# Dual_4-1_Mux.net
KiCad netlist of a schematic drawn in EAGLE
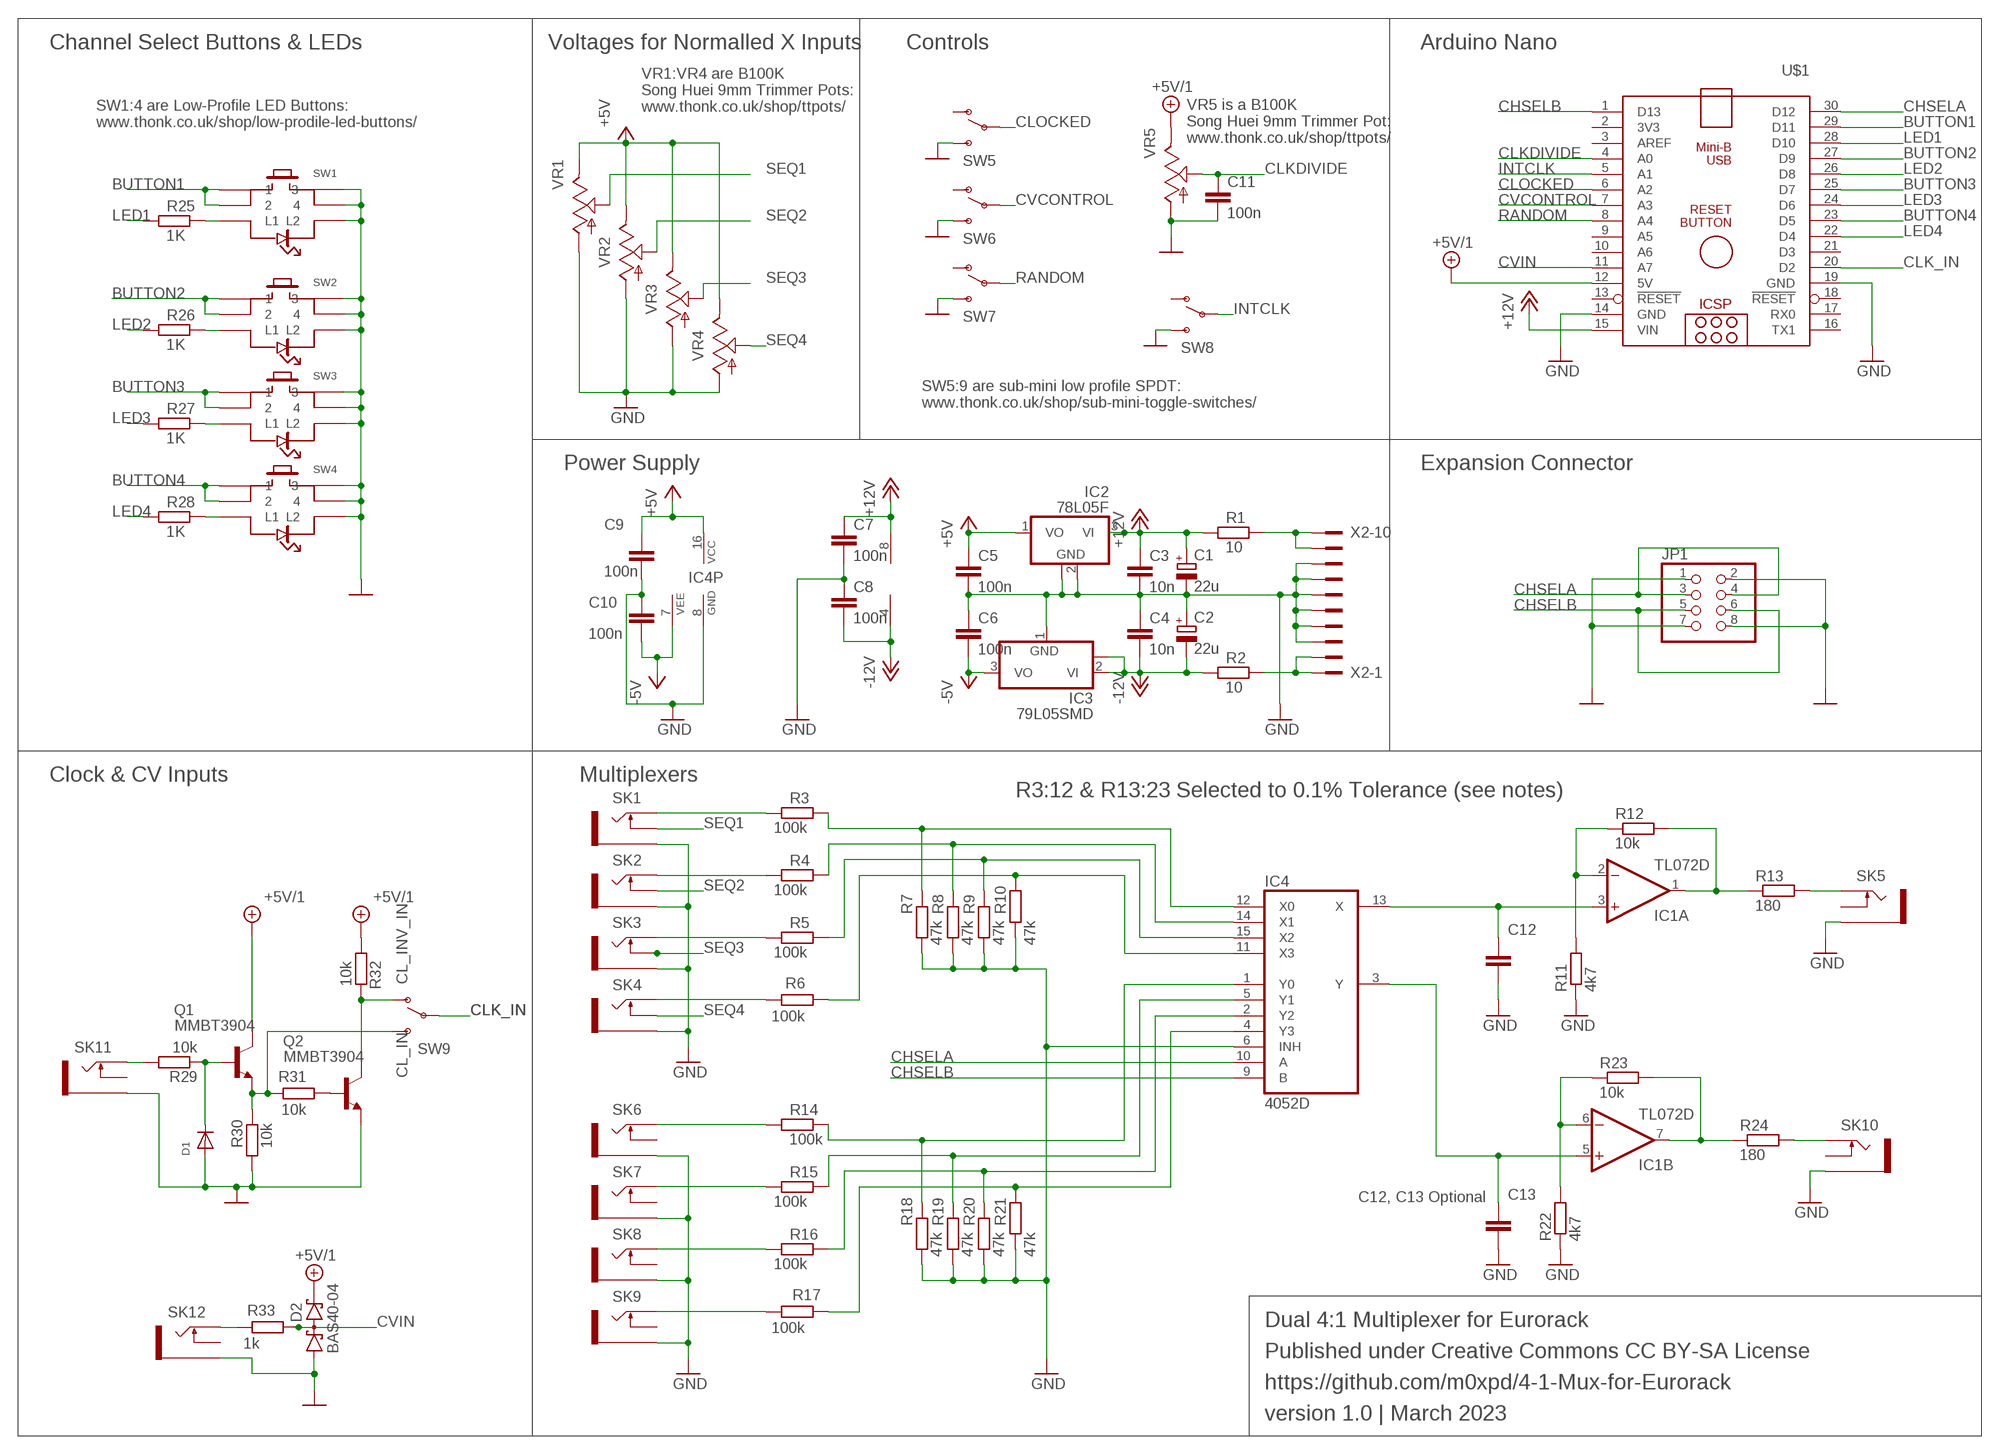
[diagram p0: schematic, sheet 1]

(export (version "E")
  (design (tool "Eeschema 10.0.6"))
  (components
    (comp (ref "C1")
      (value "22u")
      (footprint "eagle-import:153CLV-0505")
      (libsource (lib "eagle-import") (part "CPOL-EU153CLV-0505"))
    )
    (comp (ref "C2")
      (value "22u")
      (footprint "eagle-import:153CLV-0505")
      (libsource (lib "eagle-import") (part "CPOL-EU153CLV-0505"))
    )
    (comp (ref "C3")
      (value "10n")
      (footprint "eagle-import:C1206")
      (libsource (lib "eagle-import") (part "C-EUC1206"))
    )
    (comp (ref "C4")
      (value "10n")
      (footprint "eagle-import:C1206")
      (libsource (lib "eagle-import") (part "C-EUC1206"))
    )
    (comp (ref "C5")
      (value "100n")
      (footprint "eagle-import:C1206")
      (libsource (lib "eagle-import") (part "C-EUC1206"))
    )
    (comp (ref "C6")
      (value "100n")
      (footprint "eagle-import:C1206")
      (libsource (lib "eagle-import") (part "C-EUC1206"))
    )
    (comp (ref "C7")
      (value "100n")
      (footprint "eagle-import:C1206")
      (libsource (lib "eagle-import") (part "C-EUC1206"))
    )
    (comp (ref "C8")
      (value "100n")
      (footprint "eagle-import:C1206")
      (libsource (lib "eagle-import") (part "C-EUC1206"))
    )
    (comp (ref "C9")
      (value "100n")
      (footprint "eagle-import:C1206")
      (libsource (lib "eagle-import") (part "C-EUC1206"))
    )
    (comp (ref "C10")
      (value "100n")
      (footprint "eagle-import:C1206")
      (libsource (lib "eagle-import") (part "C-EUC1206"))
    )
    (comp (ref "C11")
      (value "100n")
      (footprint "eagle-import:C1206")
      (libsource (lib "eagle-import") (part "C-EUC1206"))
    )
    (comp (ref "C12")
      (value "C-EUC1206")
      (footprint "eagle-import:C1206")
      (libsource (lib "eagle-import") (part "C-EUC1206"))
    )
    (comp (ref "C13")
      (value "C-EUC1206")
      (footprint "eagle-import:C1206")
      (libsource (lib "eagle-import") (part "C-EUC1206"))
    )
    (comp (ref "D1")
      (value "DIODESOD-323F")
      (footprint "eagle-import:SOD-323F")
      (libsource (lib "eagle-import") (part "DIODESOD-323F"))
    )
    (comp (ref "D2")
      (value "BAS40-04")
      (footprint "eagle-import:SOT23")
      (libsource (lib "eagle-import") (part "BAS40-04"))
    )
    (comp (ref "IC1")
      (value "TL072D")
      (footprint "eagle-import:SO08")
      (libsource (lib "eagle-import") (part "TL072D"))
    )
    (comp (ref "IC2")
      (value "78L05F")
      (footprint "eagle-import:SOT89")
      (libsource (lib "eagle-import") (part "78LF05"))
    )
    (comp (ref "IC3")
      (value "79L05SMD")
      (footprint "eagle-import:SOT89")
      (libsource (lib "eagle-import") (part "79L05SMD"))
    )
    (comp (ref "IC4")
      (value "4052D")
      (footprint "eagle-import:SO16")
      (libsource (lib "eagle-import") (part "4052D"))
    )
    (comp (ref "JP1")
      (value "PINHD-2X4")
      (footprint "eagle-import:2X04")
      (libsource (lib "eagle-import") (part "PINHD-2X4"))
    )
    (comp (ref "Q1")
      (value "MMBT3904")
      (footprint "eagle-import:SOT23")
      (libsource (lib "eagle-import") (part "MMBT3904"))
    )
    (comp (ref "Q2")
      (value "MMBT3904")
      (footprint "eagle-import:SOT23")
      (libsource (lib "eagle-import") (part "MMBT3904"))
    )
    (comp (ref "R1")
      (value "10")
      (footprint "eagle-import:M1206")
      (libsource (lib "eagle-import") (part "R-EU_M1206"))
    )
    (comp (ref "R2")
      (value "10")
      (footprint "eagle-import:M1206")
      (libsource (lib "eagle-import") (part "R-EU_M1206"))
    )
    (comp (ref "R3")
      (value "100k")
      (footprint "eagle-import:M1206")
      (libsource (lib "eagle-import") (part "R-EU_M1206"))
    )
    (comp (ref "R4")
      (value "100k")
      (footprint "eagle-import:M1206")
      (libsource (lib "eagle-import") (part "R-EU_M1206"))
    )
    (comp (ref "R5")
      (value "100k")
      (footprint "eagle-import:M1206")
      (libsource (lib "eagle-import") (part "R-EU_M1206"))
    )
    (comp (ref "R6")
      (value "100k")
      (footprint "eagle-import:M1206")
      (libsource (lib "eagle-import") (part "R-EU_M1206"))
    )
    (comp (ref "R7")
      (value "47k")
      (footprint "eagle-import:M1206")
      (libsource (lib "eagle-import") (part "R-EU_M1206"))
    )
    (comp (ref "R8")
      (value "47k")
      (footprint "eagle-import:M1206")
      (libsource (lib "eagle-import") (part "R-EU_M1206"))
    )
    (comp (ref "R9")
      (value "47k")
      (footprint "eagle-import:M1206")
      (libsource (lib "eagle-import") (part "R-EU_M1206"))
    )
    (comp (ref "R10")
      (value "47k")
      (footprint "eagle-import:M1206")
      (libsource (lib "eagle-import") (part "R-EU_M1206"))
    )
    (comp (ref "R11")
      (value "4k7")
      (footprint "eagle-import:R1206")
      (libsource (lib "eagle-import") (part "R-EU_R1206"))
    )
    (comp (ref "R12")
      (value "10k")
      (footprint "eagle-import:R1206")
      (libsource (lib "eagle-import") (part "R-EU_R1206"))
    )
    (comp (ref "R13")
      (value "180")
      (footprint "eagle-import:M1206")
      (libsource (lib "eagle-import") (part "R-EU_M1206"))
    )
    (comp (ref "R14")
      (value "100k")
      (footprint "eagle-import:M1206")
      (libsource (lib "eagle-import") (part "R-EU_M1206"))
    )
    (comp (ref "R15")
      (value "100k")
      (footprint "eagle-import:M1206")
      (libsource (lib "eagle-import") (part "R-EU_M1206"))
    )
    (comp (ref "R16")
      (value "100k")
      (footprint "eagle-import:M1206")
      (libsource (lib "eagle-import") (part "R-EU_M1206"))
    )
    (comp (ref "R17")
      (value "100k")
      (footprint "eagle-import:M1206")
      (libsource (lib "eagle-import") (part "R-EU_M1206"))
    )
    (comp (ref "R18")
      (value "47k")
      (footprint "eagle-import:M1206")
      (libsource (lib "eagle-import") (part "R-EU_M1206"))
    )
    (comp (ref "R19")
      (value "47k")
      (footprint "eagle-import:M1206")
      (libsource (lib "eagle-import") (part "R-EU_M1206"))
    )
    (comp (ref "R20")
      (value "47k")
      (footprint "eagle-import:M1206")
      (libsource (lib "eagle-import") (part "R-EU_M1206"))
    )
    (comp (ref "R21")
      (value "47k")
      (footprint "eagle-import:M1206")
      (libsource (lib "eagle-import") (part "R-EU_M1206"))
    )
    (comp (ref "R22")
      (value "4k7")
      (footprint "eagle-import:R1206")
      (libsource (lib "eagle-import") (part "R-EU_R1206"))
    )
    (comp (ref "R23")
      (value "10k")
      (footprint "eagle-import:R1206")
      (libsource (lib "eagle-import") (part "R-EU_R1206"))
    )
    (comp (ref "R24")
      (value "180")
      (footprint "eagle-import:M1206")
      (libsource (lib "eagle-import") (part "R-EU_M1206"))
    )
    (comp (ref "R25")
      (value "1K")
      (footprint "eagle-import:M1206")
      (libsource (lib "eagle-import") (part "R-EU_M1206"))
    )
    (comp (ref "R26")
      (value "1K")
      (footprint "eagle-import:M1206")
      (libsource (lib "eagle-import") (part "R-EU_M1206"))
    )
    (comp (ref "R27")
      (value "1K")
      (footprint "eagle-import:M1206")
      (libsource (lib "eagle-import") (part "R-EU_M1206"))
    )
    (comp (ref "R28")
      (value "1K")
      (footprint "eagle-import:M1206")
      (libsource (lib "eagle-import") (part "R-EU_M1206"))
    )
    (comp (ref "R29")
      (value "10k")
      (footprint "eagle-import:R1206")
      (libsource (lib "eagle-import") (part "R-EU_R1206"))
    )
    (comp (ref "R30")
      (value "10k")
      (footprint "eagle-import:R1206")
      (libsource (lib "eagle-import") (part "R-EU_R1206"))
    )
    (comp (ref "R31")
      (value "10k")
      (footprint "eagle-import:R1206")
      (libsource (lib "eagle-import") (part "R-EU_R1206"))
    )
    (comp (ref "R32")
      (value "10k")
      (footprint "eagle-import:R1206")
      (libsource (lib "eagle-import") (part "R-EU_R1206"))
    )
    (comp (ref "R33")
      (value "1k")
      (footprint "eagle-import:M1206")
      (libsource (lib "eagle-import") (part "R-EU_M1206"))
    )
    (comp (ref "SK1")
      (value "THONKICONN_JACK")
      (footprint "eagle-import:WQP-PJ301M-12_JACK")
      (libsource (lib "eagle-import") (part "THONKICONN_JACK"))
    )
    (comp (ref "SK2")
      (value "THONKICONN_JACK")
      (footprint "eagle-import:WQP-PJ301M-12_JACK")
      (libsource (lib "eagle-import") (part "THONKICONN_JACK"))
    )
    (comp (ref "SK3")
      (value "THONKICONN_JACK")
      (footprint "eagle-import:WQP-PJ301M-12_JACK")
      (libsource (lib "eagle-import") (part "THONKICONN_JACK"))
    )
    (comp (ref "SK4")
      (value "THONKICONN_JACK")
      (footprint "eagle-import:WQP-PJ301M-12_JACK")
      (libsource (lib "eagle-import") (part "THONKICONN_JACK"))
    )
    (comp (ref "SK5")
      (value "THONKICONN_JACK")
      (footprint "eagle-import:WQP-PJ301M-12_JACK")
      (libsource (lib "eagle-import") (part "THONKICONN_JACK"))
    )
    (comp (ref "SK6")
      (value "THONKICONN_JACK")
      (footprint "eagle-import:WQP-PJ301M-12_JACK")
      (libsource (lib "eagle-import") (part "THONKICONN_JACK"))
    )
    (comp (ref "SK7")
      (value "THONKICONN_JACK")
      (footprint "eagle-import:WQP-PJ301M-12_JACK")
      (libsource (lib "eagle-import") (part "THONKICONN_JACK"))
    )
    (comp (ref "SK8")
      (value "THONKICONN_JACK")
      (footprint "eagle-import:WQP-PJ301M-12_JACK")
      (libsource (lib "eagle-import") (part "THONKICONN_JACK"))
    )
    (comp (ref "SK9")
      (value "THONKICONN_JACK")
      (footprint "eagle-import:WQP-PJ301M-12_JACK")
      (libsource (lib "eagle-import") (part "THONKICONN_JACK"))
    )
    (comp (ref "SK10")
      (value "THONKICONN_JACK")
      (footprint "eagle-import:WQP-PJ301M-12_JACK")
      (libsource (lib "eagle-import") (part "THONKICONN_JACK"))
    )
    (comp (ref "SK11")
      (value "THONKICONN_JACK")
      (footprint "eagle-import:WQP-PJ301M-12_JACK")
      (libsource (lib "eagle-import") (part "THONKICONN_JACK"))
    )
    (comp (ref "SK12")
      (value "THONKICONN_JACK")
      (footprint "eagle-import:WQP-PJ301M-12_JACK")
      (libsource (lib "eagle-import") (part "THONKICONN_JACK"))
    )
    (comp (ref "SW1")
      (value "THONK_LED_BUTTON")
      (footprint "eagle-import:LOW_PROFILE_BUTTON")
      (libsource (lib "eagle-import") (part "THONK_LED_BUTTON"))
    )
    (comp (ref "SW2")
      (value "THONK_LED_BUTTON")
      (footprint "eagle-import:LOW_PROFILE_BUTTON")
      (libsource (lib "eagle-import") (part "THONK_LED_BUTTON"))
    )
    (comp (ref "SW3")
      (value "THONK_LED_BUTTON")
      (footprint "eagle-import:LOW_PROFILE_BUTTON")
      (libsource (lib "eagle-import") (part "THONK_LED_BUTTON"))
    )
    (comp (ref "SW4")
      (value "THONK_LED_BUTTON")
      (footprint "eagle-import:LOW_PROFILE_BUTTON")
      (libsource (lib "eagle-import") (part "THONK_LED_BUTTON"))
    )
    (comp (ref "SW5")
      (value "SUBMINI_SPDT")
      (footprint "eagle-import:SUBMINI_TOGGLE")
      (libsource (lib "eagle-import") (part "SUBMINI_SPDT"))
    )
    (comp (ref "SW6")
      (value "SUBMINI_SPDT")
      (footprint "eagle-import:SUBMINI_TOGGLE")
      (libsource (lib "eagle-import") (part "SUBMINI_SPDT"))
    )
    (comp (ref "SW7")
      (value "SUBMINI_SPDT")
      (footprint "eagle-import:SUBMINI_TOGGLE")
      (libsource (lib "eagle-import") (part "SUBMINI_SPDT"))
    )
    (comp (ref "SW8")
      (value "SUBMINI_SPDT")
      (footprint "eagle-import:SUBMINI_TOGGLE")
      (libsource (lib "eagle-import") (part "SUBMINI_SPDT"))
    )
    (comp (ref "SW9")
      (value "SUBMINI_SPDT")
      (footprint "eagle-import:SUBMINI_TOGGLE")
      (libsource (lib "eagle-import") (part "SUBMINI_SPDT"))
    )
    (comp (ref "U$1")
      (value "ARDUINO_NANOARDUINO_NANO")
      (footprint "eagle-import:ARDUINO_NANO")
      (libsource (lib "eagle-import") (part "ARDUINO_NANOARDUINO_NANO"))
    )
    (comp (ref "VR1")
      (value "9MM_VERTICAL_POT")
      (footprint "eagle-import:9MM_SNAP-IN_POT")
      (libsource (lib "eagle-import") (part "9MM_VERTICAL_POT"))
    )
    (comp (ref "VR2")
      (value "9MM_VERTICAL_POT")
      (footprint "eagle-import:9MM_SNAP-IN_POT")
      (libsource (lib "eagle-import") (part "9MM_VERTICAL_POT"))
    )
    (comp (ref "VR3")
      (value "9MM_VERTICAL_POT")
      (footprint "eagle-import:9MM_SNAP-IN_POT")
      (libsource (lib "eagle-import") (part "9MM_VERTICAL_POT"))
    )
    (comp (ref "VR4")
      (value "9MM_VERTICAL_POT")
      (footprint "eagle-import:9MM_SNAP-IN_POT")
      (libsource (lib "eagle-import") (part "9MM_VERTICAL_POT"))
    )
    (comp (ref "VR5")
      (value "9MM_VERTICAL_POT")
      (footprint "eagle-import:9MM_SNAP-IN_POT")
      (libsource (lib "eagle-import") (part "9MM_VERTICAL_POT"))
    )
    (comp (ref "X2")
      (value "2510-")
      (footprint "eagle-import:PAK100_2500-10")
      (fields (field (name "MF") "3M") (field (name "MPN") "2510-6002UB"))
      (libsource (lib "eagle-import") (part "2510-"))
    )
  )
  (nets
    (net (code "1") (name "+5V") (class "Default")
      (node (ref "C5") (pin "1") (pinfunction "1_1") (pintype "passive"))
      (node (ref "C9") (pin "1") (pinfunction "1_1") (pintype "passive"))
      (node (ref "IC2") (pin "1") (pinfunction "VO_1") (pintype "passive"))
      (node (ref "IC4") (pin "16") (pinfunction "VCC_16") (pintype "power_in"))
      (node (ref "VR1") (pin "3") (pinfunction "E_3") (pintype "passive"))
      (node (ref "VR2") (pin "3") (pinfunction "E_3") (pintype "passive"))
      (node (ref "VR3") (pin "3") (pinfunction "E_3") (pintype "passive"))
      (node (ref "VR4") (pin "3") (pinfunction "E_3") (pintype "passive"))
    )
    (net (code "2") (name "+5V{slash}1") (class "Default")
      (node (ref "D2") (pin "2") (pinfunction "C2_2") (pintype "passive"))
      (node (ref "Q1") (pin "3") (pinfunction "C_3") (pintype "passive"))
      (node (ref "R32") (pin "1") (pinfunction "1_1") (pintype "passive"))
      (node (ref "U$1") (pin "12") (pinfunction "5V_12") (pintype "power_in"))
      (node (ref "VR5") (pin "3") (pinfunction "E_3") (pintype "passive"))
    )
    (net (code "3") (name "+12V") (class "Default")
      (node (ref "C1") (pin "+") (pinfunction "+_+") (pintype "passive"))
      (node (ref "C3") (pin "1") (pinfunction "1_1") (pintype "passive"))
      (node (ref "C7") (pin "1") (pinfunction "1_1") (pintype "passive"))
      (node (ref "IC1") (pin "8") (pinfunction "V+_8") (pintype "power_in"))
      (node (ref "IC2") (pin "3") (pinfunction "VI_3") (pintype "input"))
      (node (ref "R1") (pin "1") (pinfunction "1_1") (pintype "passive"))
      (node (ref "U$1") (pin "15") (pinfunction "VIN_15") (pintype "power_in"))
    )
    (net (code "4") (name "-5V") (class "Default")
      (node (ref "C10") (pin "2") (pinfunction "2_2") (pintype "passive"))
      (node (ref "C6") (pin "2") (pinfunction "2_2") (pintype "passive"))
      (node (ref "IC3") (pin "3") (pinfunction "VO_3") (pintype "passive"))
      (node (ref "IC4") (pin "7") (pinfunction "VEE_7") (pintype "power_in"))
    )
    (net (code "5") (name "-12V") (class "Default")
      (node (ref "C2") (pin "-") (pinfunction "-_-") (pintype "passive"))
      (node (ref "C4") (pin "2") (pinfunction "2_2") (pintype "passive"))
      (node (ref "C8") (pin "2") (pinfunction "2_2") (pintype "passive"))
      (node (ref "IC1") (pin "4") (pinfunction "V-_4") (pintype "power_in"))
      (node (ref "IC3") (pin "2") (pinfunction "VI_2") (pintype "input"))
      (node (ref "IC3") (pin "2@1") (pinfunction "VI_2@1") (pintype "passive"))
      (node (ref "R2") (pin "1") (pinfunction "1_1") (pintype "passive"))
    )
    (net (code "6") (name "/BUTTON1") (class "Default")
      (node (ref "SW1") (pin "P$1") (pinfunction "1_P$1") (pintype "bidirectional"))
      (node (ref "SW1") (pin "P$2") (pinfunction "2_P$2") (pintype "bidirectional"))
      (node (ref "U$1") (pin "29") (pinfunction "D11_29") (pintype "bidirectional"))
    )
    (net (code "7") (name "/BUTTON2") (class "Default")
      (node (ref "SW2") (pin "P$1") (pinfunction "1_P$1") (pintype "bidirectional"))
      (node (ref "SW2") (pin "P$2") (pinfunction "2_P$2") (pintype "bidirectional"))
      (node (ref "U$1") (pin "27") (pinfunction "D9_27") (pintype "bidirectional"))
    )
    (net (code "8") (name "/BUTTON3") (class "Default")
      (node (ref "SW3") (pin "P$1") (pinfunction "1_P$1") (pintype "bidirectional"))
      (node (ref "SW3") (pin "P$2") (pinfunction "2_P$2") (pintype "bidirectional"))
      (node (ref "U$1") (pin "25") (pinfunction "D7_25") (pintype "bidirectional"))
    )
    (net (code "9") (name "/BUTTON4") (class "Default")
      (node (ref "SW4") (pin "P$1") (pinfunction "1_P$1") (pintype "bidirectional"))
      (node (ref "SW4") (pin "P$2") (pinfunction "2_P$2") (pintype "bidirectional"))
      (node (ref "U$1") (pin "23") (pinfunction "D5_23") (pintype "bidirectional"))
    )
    (net (code "10") (name "/CHSELA") (class "Default")
      (node (ref "IC4") (pin "10") (pinfunction "A_10") (pintype "input"))
      (node (ref "JP1") (pin "3") (pinfunction "3_3") (pintype "passive"))
      (node (ref "JP1") (pin "4") (pinfunction "4_4") (pintype "passive"))
      (node (ref "U$1") (pin "30") (pinfunction "D12_30") (pintype "bidirectional"))
    )
    (net (code "11") (name "/CHSELB") (class "Default")
      (node (ref "IC4") (pin "9") (pinfunction "B_9") (pintype "input"))
      (node (ref "JP1") (pin "5") (pinfunction "5_5") (pintype "passive"))
      (node (ref "JP1") (pin "6") (pinfunction "6_6") (pintype "passive"))
      (node (ref "U$1") (pin "1") (pinfunction "D13_1") (pintype "bidirectional"))
    )
    (net (code "12") (name "/CLKDIVIDE") (class "Default")
      (node (ref "C11") (pin "1") (pinfunction "1_1") (pintype "passive"))
      (node (ref "U$1") (pin "4") (pinfunction "A0_4") (pintype "bidirectional"))
      (node (ref "VR5") (pin "2") (pinfunction "S_2") (pintype "passive"))
    )
    (net (code "13") (name "/CLK_IN") (class "Default")
      (node (ref "SW9") (pin "COM") (pinfunction "COMMON_COM") (pintype "passive"))
      (node (ref "U$1") (pin "20") (pinfunction "D2_20") (pintype "bidirectional"))
    )
    (net (code "14") (name "/CLOCKED") (class "Default")
      (node (ref "SW5") (pin "COM") (pinfunction "COMMON_COM") (pintype "passive"))
      (node (ref "U$1") (pin "6") (pinfunction "A2_6") (pintype "bidirectional"))
    )
    (net (code "15") (name "/CL_IN") (class "Default")
      (node (ref "Q1") (pin "2") (pinfunction "E_2") (pintype "passive"))
      (node (ref "R30") (pin "2") (pinfunction "2_2") (pintype "passive"))
      (node (ref "R31") (pin "2") (pinfunction "2_2") (pintype "passive"))
      (node (ref "SW9") (pin "3") (pinfunction "S_3") (pintype "passive"))
    )
    (net (code "16") (name "/CL_INV_IN") (class "Default")
      (node (ref "Q2") (pin "3") (pinfunction "C_3") (pintype "passive"))
      (node (ref "R32") (pin "2") (pinfunction "2_2") (pintype "passive"))
      (node (ref "SW9") (pin "1") (pinfunction "O_1") (pintype "passive"))
    )
    (net (code "17") (name "/CVCONTROL") (class "Default")
      (node (ref "SW6") (pin "COM") (pinfunction "COMMON_COM") (pintype "passive"))
      (node (ref "U$1") (pin "7") (pinfunction "A3_7") (pintype "bidirectional"))
    )
    (net (code "18") (name "/CVIN") (class "Default")
      (node (ref "D2") (pin "3") (pinfunction "C1A2_3") (pintype "passive"))
      (node (ref "R33") (pin "1") (pinfunction "1_1") (pintype "passive"))
      (node (ref "U$1") (pin "11") (pinfunction "A7_11") (pintype "bidirectional"))
    )
    (net (code "19") (name "/INTCLK") (class "Default")
      (node (ref "SW8") (pin "COM") (pinfunction "COMMON_COM") (pintype "passive"))
      (node (ref "U$1") (pin "5") (pinfunction "A1_5") (pintype "bidirectional"))
    )
    (net (code "20") (name "/LED1") (class "Default")
      (node (ref "R25") (pin "1") (pinfunction "1_1") (pintype "passive"))
      (node (ref "U$1") (pin "28") (pinfunction "D10_28") (pintype "bidirectional"))
    )
    (net (code "21") (name "/LED2") (class "Default")
      (node (ref "R26") (pin "1") (pinfunction "1_1") (pintype "passive"))
      (node (ref "U$1") (pin "26") (pinfunction "D8_26") (pintype "bidirectional"))
    )
    (net (code "22") (name "/LED3") (class "Default")
      (node (ref "R27") (pin "1") (pinfunction "1_1") (pintype "passive"))
      (node (ref "U$1") (pin "24") (pinfunction "D6_24") (pintype "bidirectional"))
    )
    (net (code "23") (name "/LED4") (class "Default")
      (node (ref "R28") (pin "1") (pinfunction "1_1") (pintype "passive"))
      (node (ref "U$1") (pin "22") (pinfunction "D4_22") (pintype "bidirectional"))
    )
    (net (code "24") (name "/RANDOM") (class "Default")
      (node (ref "SW7") (pin "COM") (pinfunction "COMMON_COM") (pintype "passive"))
      (node (ref "U$1") (pin "8") (pinfunction "A4_8") (pintype "bidirectional"))
    )
    (net (code "25") (name "/SEQ1") (class "Default")
      (node (ref "SK1") (pin "P$2_SWITCH") (pinfunction "SWITCH_P$2_SWITCH") (pintype "passive"))
      (node (ref "VR1") (pin "2") (pinfunction "S_2") (pintype "passive"))
    )
    (net (code "26") (name "/SEQ2") (class "Default")
      (node (ref "SK2") (pin "P$2_SWITCH") (pinfunction "SWITCH_P$2_SWITCH") (pintype "passive"))
      (node (ref "VR2") (pin "2") (pinfunction "S_2") (pintype "passive"))
    )
    (net (code "27") (name "/SEQ3") (class "Default")
      (node (ref "SK3") (pin "P$2_SWITCH") (pinfunction "SWITCH_P$2_SWITCH") (pintype "passive"))
      (node (ref "VR3") (pin "2") (pinfunction "S_2") (pintype "passive"))
    )
    (net (code "28") (name "/SEQ4") (class "Default")
      (node (ref "SK4") (pin "P$2_SWITCH") (pinfunction "SWITCH_P$2_SWITCH") (pintype "passive"))
      (node (ref "VR4") (pin "2") (pinfunction "S_2") (pintype "passive"))
    )
    (net (code "29") (name "GND") (class "Default")
      (node (ref "C1") (pin "-") (pinfunction "-_-") (pintype "passive"))
      (node (ref "C10") (pin "1") (pinfunction "1_1") (pintype "passive"))
      (node (ref "C11") (pin "2") (pinfunction "2_2") (pintype "passive"))
      (node (ref "C12") (pin "2") (pinfunction "2_2") (pintype "passive"))
      (node (ref "C13") (pin "2") (pinfunction "2_2") (pintype "passive"))
      (node (ref "C2") (pin "+") (pinfunction "+_+") (pintype "passive"))
      (node (ref "C3") (pin "2") (pinfunction "2_2") (pintype "passive"))
      (node (ref "C4") (pin "1") (pinfunction "1_1") (pintype "passive"))
      (node (ref "C5") (pin "2") (pinfunction "2_2") (pintype "passive"))
      (node (ref "C6") (pin "1") (pinfunction "1_1") (pintype "passive"))
      (node (ref "C7") (pin "2") (pinfunction "2_2") (pintype "passive"))
      (node (ref "C8") (pin "1") (pinfunction "1_1") (pintype "passive"))
      (node (ref "C9") (pin "2") (pinfunction "2_2") (pintype "passive"))
      (node (ref "D1") (pin "A") (pinfunction "A_A") (pintype "passive"))
      (node (ref "D2") (pin "1") (pinfunction "A1_1") (pintype "passive"))
      (node (ref "IC2") (pin "2") (pinfunction "GND_2") (pintype "passive"))
      (node (ref "IC2") (pin "2@1") (pinfunction "GND_2@1") (pintype "passive"))
      (node (ref "IC3") (pin "1") (pinfunction "GND_1") (pintype "passive"))
      (node (ref "IC4") (pin "6") (pinfunction "INH_6") (pintype "input"))
      (node (ref "IC4") (pin "8") (pinfunction "GND_8") (pintype "power_in"))
      (node (ref "JP1") (pin "1") (pinfunction "1_1") (pintype "passive"))
      (node (ref "JP1") (pin "2") (pinfunction "2_2") (pintype "passive"))
      (node (ref "JP1") (pin "7") (pinfunction "7_7") (pintype "passive"))
      (node (ref "JP1") (pin "8") (pinfunction "8_8") (pintype "passive"))
      (node (ref "Q2") (pin "2") (pinfunction "E_2") (pintype "passive"))
      (node (ref "R10") (pin "1") (pinfunction "1_1") (pintype "passive"))
      (node (ref "R11") (pin "1") (pinfunction "1_1") (pintype "passive"))
      (node (ref "R18") (pin "1") (pinfunction "1_1") (pintype "passive"))
      (node (ref "R19") (pin "1") (pinfunction "1_1") (pintype "passive"))
      (node (ref "R20") (pin "1") (pinfunction "1_1") (pintype "passive"))
      (node (ref "R21") (pin "1") (pinfunction "1_1") (pintype "passive"))
      (node (ref "R22") (pin "1") (pinfunction "1_1") (pintype "passive"))
      (node (ref "R30") (pin "1") (pinfunction "1_1") (pintype "passive"))
      (node (ref "R7") (pin "1") (pinfunction "1_1") (pintype "passive"))
      (node (ref "R8") (pin "1") (pinfunction "1_1") (pintype "passive"))
      (node (ref "R9") (pin "1") (pinfunction "1_1") (pintype "passive"))
      (node (ref "SK1") (pin "P$3_SLEEVE") (pinfunction "SLEEVE_P$3_SLEEVE") (pintype "passive"))
      (node (ref "SK10") (pin "P$3_SLEEVE") (pinfunction "SLEEVE_P$3_SLEEVE") (pintype "passive"))
      (node (ref "SK11") (pin "P$3_SLEEVE") (pinfunction "SLEEVE_P$3_SLEEVE") (pintype "passive"))
      (node (ref "SK12") (pin "P$3_SLEEVE") (pinfunction "SLEEVE_P$3_SLEEVE") (pintype "passive"))
      (node (ref "SK2") (pin "P$3_SLEEVE") (pinfunction "SLEEVE_P$3_SLEEVE") (pintype "passive"))
      (node (ref "SK3") (pin "P$3_SLEEVE") (pinfunction "SLEEVE_P$3_SLEEVE") (pintype "passive"))
      (node (ref "SK4") (pin "P$3_SLEEVE") (pinfunction "SLEEVE_P$3_SLEEVE") (pintype "passive"))
      (node (ref "SK5") (pin "P$3_SLEEVE") (pinfunction "SLEEVE_P$3_SLEEVE") (pintype "passive"))
      (node (ref "SK6") (pin "P$3_SLEEVE") (pinfunction "SLEEVE_P$3_SLEEVE") (pintype "passive"))
      (node (ref "SK7") (pin "P$3_SLEEVE") (pinfunction "SLEEVE_P$3_SLEEVE") (pintype "passive"))
      (node (ref "SK8") (pin "P$3_SLEEVE") (pinfunction "SLEEVE_P$3_SLEEVE") (pintype "passive"))
      (node (ref "SK9") (pin "P$3_SLEEVE") (pinfunction "SLEEVE_P$3_SLEEVE") (pintype "passive"))
      (node (ref "SW1") (pin "L$2") (pinfunction "L2_L$2") (pintype "bidirectional"))
      (node (ref "SW1") (pin "P$3") (pinfunction "3_P$3") (pintype "bidirectional"))
      (node (ref "SW1") (pin "P$4") (pinfunction "4_P$4") (pintype "bidirectional"))
      (node (ref "SW2") (pin "L$2") (pinfunction "L2_L$2") (pintype "bidirectional"))
      (node (ref "SW2") (pin "P$3") (pinfunction "3_P$3") (pintype "bidirectional"))
      (node (ref "SW2") (pin "P$4") (pinfunction "4_P$4") (pintype "bidirectional"))
      (node (ref "SW3") (pin "L$2") (pinfunction "L2_L$2") (pintype "bidirectional"))
      (node (ref "SW3") (pin "P$3") (pinfunction "3_P$3") (pintype "bidirectional"))
      (node (ref "SW3") (pin "P$4") (pinfunction "4_P$4") (pintype "bidirectional"))
      (node (ref "SW4") (pin "L$2") (pinfunction "L2_L$2") (pintype "bidirectional"))
      (node (ref "SW4") (pin "P$3") (pinfunction "3_P$3") (pintype "bidirectional"))
      (node (ref "SW4") (pin "P$4") (pinfunction "4_P$4") (pintype "bidirectional"))
      (node (ref "SW5") (pin "3") (pinfunction "S_3") (pintype "passive"))
      (node (ref "SW6") (pin "3") (pinfunction "S_3") (pintype "passive"))
      (node (ref "SW7") (pin "3") (pinfunction "S_3") (pintype "passive"))
      (node (ref "SW8") (pin "3") (pinfunction "S_3") (pintype "passive"))
      (node (ref "U$1") (pin "14") (pinfunction "GND_14") (pintype "power_in"))
      (node (ref "U$1") (pin "19") (pinfunction "GND_19") (pintype "power_in"))
      (node (ref "VR1") (pin "1") (pinfunction "A_1") (pintype "passive"))
      (node (ref "VR2") (pin "1") (pinfunction "A_1") (pintype "passive"))
      (node (ref "VR3") (pin "1") (pinfunction "A_1") (pintype "passive"))
      (node (ref "VR4") (pin "1") (pinfunction "A_1") (pintype "passive"))
      (node (ref "VR5") (pin "1") (pinfunction "A_1") (pintype "passive"))
      (node (ref "X2") (pin "3") (pinfunction "KL_3") (pintype "passive"))
      (node (ref "X2") (pin "4") (pinfunction "KL_4") (pintype "passive"))
      (node (ref "X2") (pin "5") (pinfunction "KL_5") (pintype "passive"))
      (node (ref "X2") (pin "6") (pinfunction "KL_6") (pintype "passive"))
      (node (ref "X2") (pin "7") (pinfunction "KL_7") (pintype "passive"))
      (node (ref "X2") (pin "8") (pinfunction "KL_8") (pintype "passive"))
    )
    (net (code "30") (name "Net-(IC1A-+IN)") (class "Default")
      (node (ref "C12") (pin "1") (pinfunction "1_1") (pintype "passive"))
      (node (ref "IC1") (pin "3") (pinfunction "+IN_3") (pintype "input"))
      (node (ref "IC4") (pin "13") (pinfunction "X_13") (pintype "bidirectional"))
    )
    (net (code "31") (name "Net-(IC1A--IN)") (class "Default")
      (node (ref "IC1") (pin "2") (pinfunction "-IN_2") (pintype "input"))
      (node (ref "R11") (pin "2") (pinfunction "2_2") (pintype "passive"))
      (node (ref "R12") (pin "1") (pinfunction "1_1") (pintype "passive"))
    )
    (net (code "32") (name "Net-(IC1A-OUT)") (class "Default")
      (node (ref "IC1") (pin "1") (pinfunction "OUT_1") (pintype "output"))
      (node (ref "R12") (pin "2") (pinfunction "2_2") (pintype "passive"))
      (node (ref "R13") (pin "1") (pinfunction "1_1") (pintype "passive"))
    )
    (net (code "33") (name "Net-(IC1B-+IN)") (class "Default")
      (node (ref "C13") (pin "1") (pinfunction "1_1") (pintype "passive"))
      (node (ref "IC1") (pin "5") (pinfunction "+IN_5") (pintype "input"))
      (node (ref "IC4") (pin "3") (pinfunction "Y_3") (pintype "bidirectional"))
    )
    (net (code "34") (name "Net-(IC1B--IN)") (class "Default")
      (node (ref "IC1") (pin "6") (pinfunction "-IN_6") (pintype "input"))
      (node (ref "R22") (pin "2") (pinfunction "2_2") (pintype "passive"))
      (node (ref "R23") (pin "1") (pinfunction "1_1") (pintype "passive"))
    )
    (net (code "35") (name "Net-(IC1B-OUT)") (class "Default")
      (node (ref "IC1") (pin "7") (pinfunction "OUT_7") (pintype "output"))
      (node (ref "R23") (pin "2") (pinfunction "2_2") (pintype "passive"))
      (node (ref "R24") (pin "1") (pinfunction "1_1") (pintype "passive"))
    )
    (net (code "36") (name "Net-(IC4A-X0)") (class "Default")
      (node (ref "IC4") (pin "12") (pinfunction "X0_12") (pintype "bidirectional"))
      (node (ref "R3") (pin "2") (pinfunction "2_2") (pintype "passive"))
      (node (ref "R7") (pin "2") (pinfunction "2_2") (pintype "passive"))
    )
    (net (code "37") (name "Net-(IC4A-X1)") (class "Default")
      (node (ref "IC4") (pin "14") (pinfunction "X1_14") (pintype "bidirectional"))
      (node (ref "R4") (pin "2") (pinfunction "2_2") (pintype "passive"))
      (node (ref "R8") (pin "2") (pinfunction "2_2") (pintype "passive"))
    )
    (net (code "38") (name "Net-(IC4A-X2)") (class "Default")
      (node (ref "IC4") (pin "15") (pinfunction "X2_15") (pintype "bidirectional"))
      (node (ref "R5") (pin "2") (pinfunction "2_2") (pintype "passive"))
      (node (ref "R9") (pin "2") (pinfunction "2_2") (pintype "passive"))
    )
    (net (code "39") (name "Net-(IC4A-X3)") (class "Default")
      (node (ref "IC4") (pin "11") (pinfunction "X3_11") (pintype "bidirectional"))
      (node (ref "R10") (pin "2") (pinfunction "2_2") (pintype "passive"))
      (node (ref "R6") (pin "1") (pinfunction "1_1") (pintype "passive"))
    )
    (net (code "40") (name "Net-(IC4A-Y0)") (class "Default")
      (node (ref "IC4") (pin "1") (pinfunction "Y0_1") (pintype "bidirectional"))
      (node (ref "R14") (pin "2") (pinfunction "2_2") (pintype "passive"))
      (node (ref "R18") (pin "2") (pinfunction "2_2") (pintype "passive"))
    )
    (net (code "41") (name "Net-(IC4A-Y1)") (class "Default")
      (node (ref "IC4") (pin "5") (pinfunction "Y1_5") (pintype "bidirectional"))
      (node (ref "R15") (pin "2") (pinfunction "2_2") (pintype "passive"))
      (node (ref "R19") (pin "2") (pinfunction "2_2") (pintype "passive"))
    )
    (net (code "42") (name "Net-(IC4A-Y2)") (class "Default")
      (node (ref "IC4") (pin "2") (pinfunction "Y2_2") (pintype "bidirectional"))
      (node (ref "R16") (pin "2") (pinfunction "2_2") (pintype "passive"))
      (node (ref "R20") (pin "2") (pinfunction "2_2") (pintype "passive"))
    )
    (net (code "43") (name "Net-(IC4A-Y3)") (class "Default")
      (node (ref "IC4") (pin "4") (pinfunction "Y3_4") (pintype "bidirectional"))
      (node (ref "R17") (pin "1") (pinfunction "1_1") (pintype "passive"))
      (node (ref "R21") (pin "2") (pinfunction "2_2") (pintype "passive"))
    )
    (net (code "44") (name "Net-(Q1-B)") (class "Default")
      (node (ref "D1") (pin "C") (pinfunction "C_C") (pintype "passive"))
      (node (ref "Q1") (pin "1") (pinfunction "B_1") (pintype "passive"))
      (node (ref "R29") (pin "1") (pinfunction "1_1") (pintype "passive"))
    )
    (net (code "45") (name "Net-(Q2-B)") (class "Default")
      (node (ref "Q2") (pin "1") (pinfunction "B_1") (pintype "passive"))
      (node (ref "R31") (pin "1") (pinfunction "1_1") (pintype "passive"))
    )
    (net (code "46") (name "Net-(SK1-TIP)") (class "Default")
      (node (ref "R3") (pin "1") (pinfunction "1_1") (pintype "passive"))
      (node (ref "SK1") (pin "P$1_TIP") (pinfunction "TIP_P$1_TIP") (pintype "passive"))
    )
    (net (code "47") (name "Net-(SK2-TIP)") (class "Default")
      (node (ref "R4") (pin "1") (pinfunction "1_1") (pintype "passive"))
      (node (ref "SK2") (pin "P$1_TIP") (pinfunction "TIP_P$1_TIP") (pintype "passive"))
    )
    (net (code "48") (name "Net-(SK3-TIP)") (class "Default")
      (node (ref "R5") (pin "1") (pinfunction "1_1") (pintype "passive"))
      (node (ref "SK3") (pin "P$1_TIP") (pinfunction "TIP_P$1_TIP") (pintype "passive"))
    )
    (net (code "49") (name "Net-(SK4-TIP)") (class "Default")
      (node (ref "R6") (pin "2") (pinfunction "2_2") (pintype "passive"))
      (node (ref "SK4") (pin "P$1_TIP") (pinfunction "TIP_P$1_TIP") (pintype "passive"))
    )
    (net (code "50") (name "Net-(SK5-TIP)") (class "Default")
      (node (ref "R13") (pin "2") (pinfunction "2_2") (pintype "passive"))
      (node (ref "SK5") (pin "P$1_TIP") (pinfunction "TIP_P$1_TIP") (pintype "passive"))
    )
    (net (code "51") (name "Net-(SK6-TIP)") (class "Default")
      (node (ref "R14") (pin "1") (pinfunction "1_1") (pintype "passive"))
      (node (ref "SK6") (pin "P$1_TIP") (pinfunction "TIP_P$1_TIP") (pintype "passive"))
    )
    (net (code "52") (name "Net-(SK7-TIP)") (class "Default")
      (node (ref "R15") (pin "1") (pinfunction "1_1") (pintype "passive"))
      (node (ref "SK7") (pin "P$1_TIP") (pinfunction "TIP_P$1_TIP") (pintype "passive"))
    )
    (net (code "53") (name "Net-(SK8-TIP)") (class "Default")
      (node (ref "R16") (pin "1") (pinfunction "1_1") (pintype "passive"))
      (node (ref "SK8") (pin "P$1_TIP") (pinfunction "TIP_P$1_TIP") (pintype "passive"))
    )
    (net (code "54") (name "Net-(SK9-TIP)") (class "Default")
      (node (ref "R17") (pin "2") (pinfunction "2_2") (pintype "passive"))
      (node (ref "SK9") (pin "P$1_TIP") (pinfunction "TIP_P$1_TIP") (pintype "passive"))
    )
    (net (code "55") (name "Net-(SK10-TIP)") (class "Default")
      (node (ref "R24") (pin "2") (pinfunction "2_2") (pintype "passive"))
      (node (ref "SK10") (pin "P$1_TIP") (pinfunction "TIP_P$1_TIP") (pintype "passive"))
    )
    (net (code "56") (name "Net-(SK11-TIP)") (class "Default")
      (node (ref "R29") (pin "2") (pinfunction "2_2") (pintype "passive"))
      (node (ref "SK11") (pin "P$1_TIP") (pinfunction "TIP_P$1_TIP") (pintype "passive"))
    )
    (net (code "57") (name "Net-(SK12-TIP)") (class "Default")
      (node (ref "R33") (pin "2") (pinfunction "2_2") (pintype "passive"))
      (node (ref "SK12") (pin "P$1_TIP") (pinfunction "TIP_P$1_TIP") (pintype "passive"))
    )
    (net (code "58") (name "Net-(SW1-L1)") (class "Default")
      (node (ref "R25") (pin "2") (pinfunction "2_2") (pintype "passive"))
      (node (ref "SW1") (pin "L$1") (pinfunction "L1_L$1") (pintype "bidirectional"))
    )
    (net (code "59") (name "Net-(SW2-L1)") (class "Default")
      (node (ref "R26") (pin "2") (pinfunction "2_2") (pintype "passive"))
      (node (ref "SW2") (pin "L$1") (pinfunction "L1_L$1") (pintype "bidirectional"))
    )
    (net (code "60") (name "Net-(SW3-L1)") (class "Default")
      (node (ref "R27") (pin "2") (pinfunction "2_2") (pintype "passive"))
      (node (ref "SW3") (pin "L$1") (pinfunction "L1_L$1") (pintype "bidirectional"))
    )
    (net (code "61") (name "Net-(SW4-L1)") (class "Default")
      (node (ref "R28") (pin "2") (pinfunction "2_2") (pintype "passive"))
      (node (ref "SW4") (pin "L$1") (pinfunction "L1_L$1") (pintype "bidirectional"))
    )
    (net (code "62") (name "Net-(X2A-KL)") (class "Default")
      (node (ref "R2") (pin "2") (pinfunction "2_2") (pintype "passive"))
      (node (ref "X2") (pin "1") (pinfunction "KL_1") (pintype "passive"))
      (node (ref "X2") (pin "2") (pinfunction "KL_2") (pintype "passive"))
    )
    (net (code "63") (name "Net-(X2B-KL)") (class "Default")
      (node (ref "R1") (pin "2") (pinfunction "2_2") (pintype "passive"))
      (node (ref "X2") (pin "10") (pinfunction "KL_10") (pintype "passive"))
      (node (ref "X2") (pin "9") (pinfunction "KL_9") (pintype "passive"))
    )
    (net (code "64") (name "unconnected-(SK5-SWITCH-PadP$2_SWITCH)") (class "Default")
      (node (ref "SK5") (pin "P$2_SWITCH") (pinfunction "SWITCH_P$2_SWITCH") (pintype "passive"))
    )
    (net (code "65") (name "unconnected-(SK6-SWITCH-PadP$2_SWITCH)") (class "Default")
      (node (ref "SK6") (pin "P$2_SWITCH") (pinfunction "SWITCH_P$2_SWITCH") (pintype "passive"))
    )
    (net (code "66") (name "unconnected-(SK7-SWITCH-PadP$2_SWITCH)") (class "Default")
      (node (ref "SK7") (pin "P$2_SWITCH") (pinfunction "SWITCH_P$2_SWITCH") (pintype "passive"))
    )
    (net (code "67") (name "unconnected-(SK8-SWITCH-PadP$2_SWITCH)") (class "Default")
      (node (ref "SK8") (pin "P$2_SWITCH") (pinfunction "SWITCH_P$2_SWITCH") (pintype "passive"))
    )
    (net (code "68") (name "unconnected-(SK9-SWITCH-PadP$2_SWITCH)") (class "Default")
      (node (ref "SK9") (pin "P$2_SWITCH") (pinfunction "SWITCH_P$2_SWITCH") (pintype "passive"))
    )
    (net (code "69") (name "unconnected-(SK10-SWITCH-PadP$2_SWITCH)") (class "Default")
      (node (ref "SK10") (pin "P$2_SWITCH") (pinfunction "SWITCH_P$2_SWITCH") (pintype "passive"))
    )
    (net (code "70") (name "unconnected-(SK11-SWITCH-PadP$2_SWITCH)") (class "Default")
      (node (ref "SK11") (pin "P$2_SWITCH") (pinfunction "SWITCH_P$2_SWITCH") (pintype "passive"))
    )
    (net (code "71") (name "unconnected-(SK12-SWITCH-PadP$2_SWITCH)") (class "Default")
      (node (ref "SK12") (pin "P$2_SWITCH") (pinfunction "SWITCH_P$2_SWITCH") (pintype "passive"))
    )
    (net (code "72") (name "unconnected-(SW5-O-Pad1)") (class "Default")
      (node (ref "SW5") (pin "1") (pinfunction "O_1") (pintype "passive"))
    )
    (net (code "73") (name "unconnected-(SW6-O-Pad1)") (class "Default")
      (node (ref "SW6") (pin "1") (pinfunction "O_1") (pintype "passive"))
    )
    (net (code "74") (name "unconnected-(SW7-O-Pad1)") (class "Default")
      (node (ref "SW7") (pin "1") (pinfunction "O_1") (pintype "passive"))
    )
    (net (code "75") (name "unconnected-(SW8-O-Pad1)") (class "Default")
      (node (ref "SW8") (pin "1") (pinfunction "O_1") (pintype "passive"))
    )
    (net (code "76") (name "unconnected-(U$1-3V3-Pad2)") (class "Default")
      (node (ref "U$1") (pin "2") (pinfunction "3V3_2") (pintype "output"))
    )
    (net (code "77") (name "unconnected-(U$1-A5-Pad9)") (class "Default")
      (node (ref "U$1") (pin "9") (pinfunction "A5_9") (pintype "bidirectional"))
    )
    (net (code "78") (name "unconnected-(U$1-A6-Pad10)") (class "Default")
      (node (ref "U$1") (pin "10") (pinfunction "A6_10") (pintype "bidirectional"))
    )
    (net (code "79") (name "unconnected-(U$1-AREF-Pad3)") (class "Default")
      (node (ref "U$1") (pin "3") (pinfunction "AREF_3") (pintype "input"))
    )
    (net (code "80") (name "unconnected-(U$1-D3-Pad21)") (class "Default")
      (node (ref "U$1") (pin "21") (pinfunction "D3_21") (pintype "bidirectional"))
    )
    (net (code "81") (name "unconnected-(U$1-RX0-Pad17)") (class "Default")
      (node (ref "U$1") (pin "17") (pinfunction "RX0_17") (pintype "bidirectional"))
    )
    (net (code "82") (name "unconnected-(U$1-TX1-Pad16)") (class "Default")
      (node (ref "U$1") (pin "16") (pinfunction "TX1_16") (pintype "bidirectional"))
    )
    (net (code "83") (name "unconnected-(U$1-~{RESET}-Pad13)") (class "Default")
      (node (ref "U$1") (pin "13") (pinfunction "~{RESET}_13") (pintype "input"))
    )
    (net (code "84") (name "unconnected-(U$1-~{RESET}-Pad18)") (class "Default")
      (node (ref "U$1") (pin "18") (pinfunction "~{RESET}_18") (pintype "input"))
    )
  )
)
